# MB_power_supply.net
KiCad netlist of a schematic drawn in Altium Designer
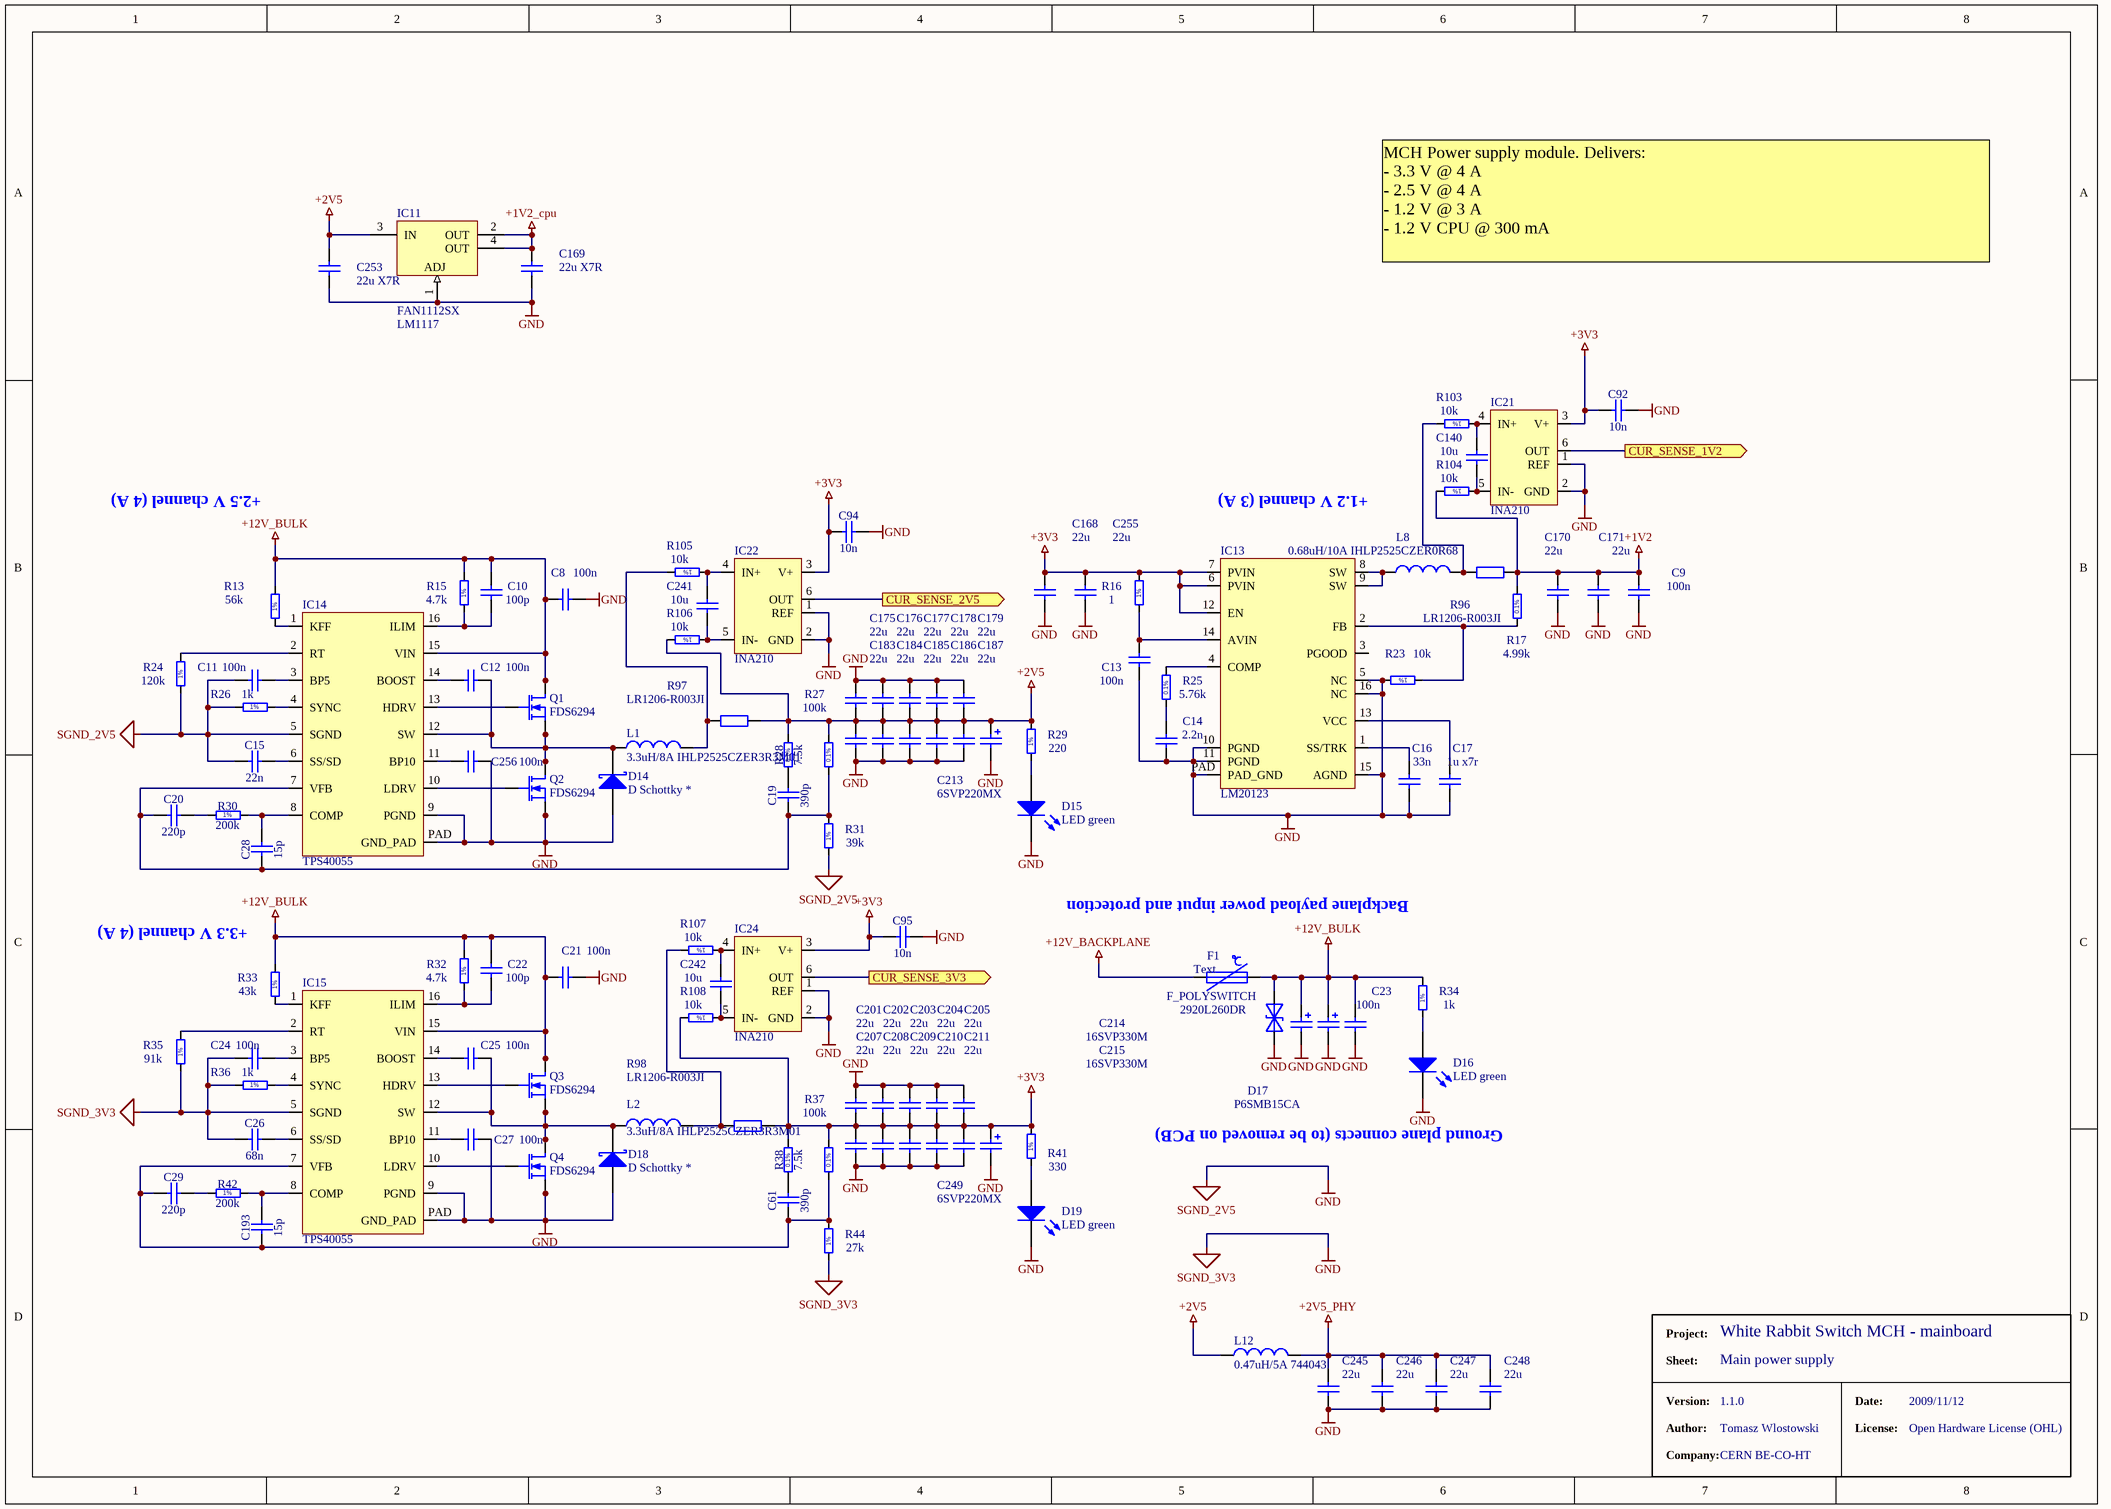
[diagram p0: MB_power_supply.SchDoc]

(export (version "E")
  (design (tool "Eeschema 10.0.6"))
  (components
    (comp (ref "C8")
      (value "100n")
      (footprint "CAPC1608X87N")
      (description "Non-polarised capacitor")
      (fields (field (name "PART NUMBER") "CC0603_100NF_50V_10%_X7R") (field (name "VOLTAGE") "50V"))
      (libsource (lib "Capacitors") (part "Capacitor - non polarized"))
    )
    (comp (ref "C9")
      (value "100n")
      (footprint "CAPC1608X87N")
      (description "Non-polarised capacitor")
      (fields (field (name "PART NUMBER") "CC0603_100NF_50V_10%_X7R") (field (name "VOLTAGE") "50V"))
      (libsource (lib "Capacitors") (part "Capacitor - non polarized"))
    )
    (comp (ref "C10")
      (value "100p")
      (footprint "CAPC1608X87N")
      (description "Non-polarised capacitor")
      (fields (field (name "PART NUMBER") "CC0603_100PF_50V_5%_NP0") (field (name "VOLTAGE") "50V"))
      (libsource (lib "Capacitors") (part "Capacitor - non polarized"))
    )
    (comp (ref "C11")
      (value "100n")
      (footprint "CAPC1608X87N")
      (description "Non-polarised capacitor")
      (fields (field (name "PART NUMBER") "CC0603_100NF_50V_10%_X7R") (field (name "VOLTAGE") "50V"))
      (libsource (lib "Capacitors") (part "Capacitor - non polarized"))
    )
    (comp (ref "C12")
      (value "100n")
      (footprint "CAPC1608X87N")
      (description "Non-polarised capacitor")
      (fields (field (name "PART NUMBER") "CC0603_100NF_50V_10%_X7R") (field (name "VOLTAGE") "50V"))
      (libsource (lib "Capacitors") (part "Capacitor - non polarized"))
    )
    (comp (ref "C13")
      (value "100n")
      (footprint "CAPC1608X87N")
      (description "Non-polarised capacitor")
      (fields (field (name "PART NUMBER") "CC0603_100NF_50V_10%_X7R") (field (name "VOLTAGE") "50V"))
      (libsource (lib "Capacitors") (part "Capacitor - non polarized"))
    )
    (comp (ref "C14")
      (value "2.2n")
      (footprint "CAPC1608X87N")
      (description "Non-polarised capacitor")
      (fields (field (name "PART NUMBER") "CC0603_2.2NF_50V_10%_X7R") (field (name "VOLTAGE") "50V"))
      (libsource (lib "Capacitors") (part "Capacitor - non polarized"))
    )
    (comp (ref "C15")
      (value "22n")
      (footprint "CAPC1608X87N")
      (description "Non-polarised capacitor")
      (fields (field (name "PART NUMBER") "CC0603_22NF_50V_10%_X7R") (field (name "VOLTAGE") "50V"))
      (libsource (lib "Capacitors") (part "Capacitor - non polarized"))
    )
    (comp (ref "C16")
      (value "33n")
      (footprint "CAPC1608X87N")
      (description "Non-polarised capacitor")
      (fields (field (name "PART NUMBER") "CC0603_33NF_25V_10%_X7R") (field (name "VOLTAGE") "25V"))
      (libsource (lib "Capacitors") (part "Capacitor - non polarized"))
    )
    (comp (ref "C17")
      (value "1u x7r")
      (footprint "CAPC1608X87N")
      (description "Non-polarised capacitor")
      (fields (field (name "PART NUMBER") "CC0603_1.0uF_16V_10%_X7R") (field (name "VOLTAGE") "16V"))
      (libsource (lib "Capacitors") (part "Capacitor - non polarized"))
    )
    (comp (ref "C19")
      (value "390p")
      (footprint "CAPC1608X87N")
      (description "Non-polarised capacitor")
      (fields (field (name "PART NUMBER") "CC0603_390PF_50V_5%_NP0") (field (name "VOLTAGE") "50V"))
      (libsource (lib "Capacitors") (part "Capacitor - non polarized"))
    )
    (comp (ref "C20")
      (value "220p")
      (footprint "CAPC1608X87N")
      (description "Non-polarised capacitor")
      (fields (field (name "PART NUMBER") "CC0603_220PF_50V_5%_NP0") (field (name "VOLTAGE") "50V"))
      (libsource (lib "Capacitors") (part "Capacitor - non polarized"))
    )
    (comp (ref "C21")
      (value "100n")
      (footprint "CAPC1608X87N")
      (description "Non-polarised capacitor")
      (fields (field (name "PART NUMBER") "CC0603_100NF_50V_10%_X7R") (field (name "VOLTAGE") "50V"))
      (libsource (lib "Capacitors") (part "Capacitor - non polarized"))
    )
    (comp (ref "C22")
      (value "100p")
      (footprint "CAPC1608X87N")
      (description "Non-polarised capacitor")
      (fields (field (name "PART NUMBER") "CC0603_100PF_50V_5%_NP0") (field (name "VOLTAGE") "50V"))
      (libsource (lib "Capacitors") (part "Capacitor - non polarized"))
    )
    (comp (ref "C23")
      (value "100n")
      (footprint "CAPC1608X87N")
      (description "Non-polarised capacitor")
      (fields (field (name "PART NUMBER") "CC0603_100NF_50V_10%_X7R") (field (name "VOLTAGE") "50V"))
      (libsource (lib "Capacitors") (part "Capacitor - non polarized"))
    )
    (comp (ref "C24")
      (value "100n")
      (footprint "CAPC1608X87N")
      (description "Non-polarised capacitor")
      (fields (field (name "PART NUMBER") "CC0603_100NF_50V_10%_X7R") (field (name "VOLTAGE") "50V"))
      (libsource (lib "Capacitors") (part "Capacitor - non polarized"))
    )
    (comp (ref "C25")
      (value "100n")
      (footprint "CAPC1608X87N")
      (description "Non-polarised capacitor")
      (fields (field (name "PART NUMBER") "CC0603_100NF_50V_10%_X7R") (field (name "VOLTAGE") "50V"))
      (libsource (lib "Capacitors") (part "Capacitor - non polarized"))
    )
    (comp (ref "C26")
      (value "68n")
      (footprint "CAPC1608X87N")
      (description "Non-polarised capacitor")
      (fields (field (name "PART NUMBER") "CC0603_68NF_16V_10%_X7R") (field (name "VOLTAGE") "16V"))
      (libsource (lib "Capacitors") (part "Capacitor - non polarized"))
    )
    (comp (ref "C27")
      (value "100n")
      (footprint "CAPC1608X87N")
      (description "Non-polarised capacitor")
      (fields (field (name "PART NUMBER") "CC0603_100NF_50V_10%_X7R") (field (name "VOLTAGE") "50V"))
      (libsource (lib "Capacitors") (part "Capacitor - non polarized"))
    )
    (comp (ref "C28")
      (value "15p")
      (footprint "CAPC1608X87N")
      (description "Non-polarised capacitor")
      (fields (field (name "PART NUMBER") "CC0603_15PF_50V_5%_NP0") (field (name "VOLTAGE") "50V"))
      (libsource (lib "Capacitors") (part "Capacitor - non polarized"))
    )
    (comp (ref "C29")
      (value "220p")
      (footprint "CAPC1608X87N")
      (description "Non-polarised capacitor")
      (fields (field (name "PART NUMBER") "CC0603_220PF_50V_5%_NP0") (field (name "VOLTAGE") "50V"))
      (libsource (lib "Capacitors") (part "Capacitor - non polarized"))
    )
    (comp (ref "C61")
      (value "390p")
      (footprint "CAPC1608X87N")
      (description "Non-polarised capacitor")
      (fields (field (name "PART NUMBER") "CC0603_390PF_50V_5%_NP0") (field (name "VOLTAGE") "50V"))
      (libsource (lib "Capacitors") (part "Capacitor - non polarized"))
    )
    (comp (ref "C92")
      (value "10n")
      (footprint "CAPC1608X87N")
      (description "Non-polarised capacitor")
      (fields (field (name "PART NUMBER") "CC0603_10NF_50V_10%_X7R") (field (name "VOLTAGE") "50V"))
      (libsource (lib "Capacitors") (part "Capacitor - non polarized"))
    )
    (comp (ref "C94")
      (value "10n")
      (footprint "CAPC1608X87N")
      (description "Non-polarised capacitor")
      (fields (field (name "PART NUMBER") "CC0603_10NF_50V_10%_X7R") (field (name "VOLTAGE") "50V"))
      (libsource (lib "Capacitors") (part "Capacitor - non polarized"))
    )
    (comp (ref "C95")
      (value "10n")
      (footprint "CAPC1608X87N")
      (description "Non-polarised capacitor")
      (fields (field (name "PART NUMBER") "CC0603_10NF_50V_10%_X7R") (field (name "VOLTAGE") "50V"))
      (libsource (lib "Capacitors") (part "Capacitor - non polarized"))
    )
    (comp (ref "C140")
      (value "10u")
      (footprint "CAPC1608X87N")
      (description "Non-polarised capacitor")
      (fields (field (name "PART NUMBER") "CC0603_10uF_6.3V_20%_X5R") (field (name "VOLTAGE") "6.3V"))
      (libsource (lib "Capacitors") (part "Capacitor - non polarized"))
    )
    (comp (ref "C168")
      (value "22u")
      (footprint "CC3216-1206")
      (description "Capacitor")
      (fields (field (name "Comment") "22u X7R"))
      (libsource (lib "wr_switch") (part "Cap"))
    )
    (comp (ref "C169")
      (value "22u X7R")
      (footprint "CC3216-1206")
      (description "Capacitor")
      (libsource (lib "wr_switch") (part "Cap"))
    )
    (comp (ref "C170")
      (value "22u")
      (footprint "CC3216-1206")
      (description "Capacitor")
      (fields (field (name "Comment") "22u X7R"))
      (libsource (lib "wr_switch") (part "Cap"))
    )
    (comp (ref "C171")
      (value "22u")
      (footprint "CC3216-1206")
      (description "Capacitor")
      (fields (field (name "Comment") "22u X7R"))
      (libsource (lib "wr_switch") (part "Cap"))
    )
    (comp (ref "C175")
      (value "22u")
      (footprint "CC3216-1206")
      (description "Capacitor")
      (fields (field (name "Comment") "22u X7R"))
      (libsource (lib "wr_switch") (part "Cap"))
    )
    (comp (ref "C176")
      (value "22u")
      (footprint "CC3216-1206")
      (description "Capacitor")
      (fields (field (name "Comment") "22u X7R"))
      (libsource (lib "wr_switch") (part "Cap"))
    )
    (comp (ref "C177")
      (value "22u")
      (footprint "CC3216-1206")
      (description "Capacitor")
      (fields (field (name "Comment") "22u X7R"))
      (libsource (lib "wr_switch") (part "Cap"))
    )
    (comp (ref "C178")
      (value "22u")
      (footprint "CC3216-1206")
      (description "Capacitor")
      (fields (field (name "Comment") "22u X7R"))
      (libsource (lib "wr_switch") (part "Cap"))
    )
    (comp (ref "C179")
      (value "22u")
      (footprint "CC3216-1206")
      (description "Capacitor")
      (fields (field (name "Comment") "22u X7R"))
      (libsource (lib "wr_switch") (part "Cap"))
    )
    (comp (ref "C183")
      (value "22u")
      (footprint "CC3216-1206")
      (description "Capacitor")
      (fields (field (name "Comment") "22u X7R"))
      (libsource (lib "wr_switch") (part "Cap"))
    )
    (comp (ref "C184")
      (value "22u")
      (footprint "CC3216-1206")
      (description "Capacitor")
      (fields (field (name "Comment") "22u X7R"))
      (libsource (lib "wr_switch") (part "Cap"))
    )
    (comp (ref "C185")
      (value "22u")
      (footprint "CC3216-1206")
      (description "Capacitor")
      (fields (field (name "Comment") "22u X7R"))
      (libsource (lib "wr_switch") (part "Cap"))
    )
    (comp (ref "C186")
      (value "22u")
      (footprint "CC3216-1206")
      (description "Capacitor")
      (fields (field (name "Comment") "22u X7R"))
      (libsource (lib "wr_switch") (part "Cap"))
    )
    (comp (ref "C187")
      (value "22u")
      (footprint "CC3216-1206")
      (description "Capacitor")
      (fields (field (name "Comment") "22u X7R"))
      (libsource (lib "wr_switch") (part "Cap"))
    )
    (comp (ref "C193")
      (value "15p")
      (footprint "CAPC1608X87N")
      (description "Non-polarised capacitor")
      (fields (field (name "PART NUMBER") "CC0603_15PF_50V_5%_NP0") (field (name "VOLTAGE") "50V"))
      (libsource (lib "Capacitors") (part "Capacitor - non polarized"))
    )
    (comp (ref "C201")
      (value "22u")
      (footprint "CC3216-1206")
      (description "Capacitor")
      (fields (field (name "Comment") "22u X7R"))
      (libsource (lib "wr_switch") (part "Cap"))
    )
    (comp (ref "C202")
      (value "22u")
      (footprint "CC3216-1206")
      (description "Capacitor")
      (fields (field (name "Comment") "22u X7R"))
      (libsource (lib "wr_switch") (part "Cap"))
    )
    (comp (ref "C203")
      (value "22u")
      (footprint "CC3216-1206")
      (description "Capacitor")
      (fields (field (name "Comment") "22u X7R"))
      (libsource (lib "wr_switch") (part "Cap"))
    )
    (comp (ref "C204")
      (value "22u")
      (footprint "CC3216-1206")
      (description "Capacitor")
      (fields (field (name "Comment") "22u X7R"))
      (libsource (lib "wr_switch") (part "Cap"))
    )
    (comp (ref "C205")
      (value "22u")
      (footprint "CC3216-1206")
      (description "Capacitor")
      (fields (field (name "Comment") "22u X7R"))
      (libsource (lib "wr_switch") (part "Cap"))
    )
    (comp (ref "C207")
      (value "22u")
      (footprint "CC3216-1206")
      (description "Capacitor")
      (fields (field (name "Comment") "22u X7R"))
      (libsource (lib "wr_switch") (part "Cap"))
    )
    (comp (ref "C208")
      (value "22u")
      (footprint "CC3216-1206")
      (description "Capacitor")
      (fields (field (name "Comment") "22u X7R"))
      (libsource (lib "wr_switch") (part "Cap"))
    )
    (comp (ref "C209")
      (value "22u")
      (footprint "CC3216-1206")
      (description "Capacitor")
      (fields (field (name "Comment") "22u X7R"))
      (libsource (lib "wr_switch") (part "Cap"))
    )
    (comp (ref "C210")
      (value "22u")
      (footprint "CC3216-1206")
      (description "Capacitor")
      (fields (field (name "Comment") "22u X7R"))
      (libsource (lib "wr_switch") (part "Cap"))
    )
    (comp (ref "C211")
      (value "22u")
      (footprint "CC3216-1206")
      (description "Capacitor")
      (fields (field (name "Comment") "22u X7R"))
      (libsource (lib "wr_switch") (part "Cap"))
    )
    (comp (ref "C213")
      (value "6SVP220MX")
      (footprint "OSCON_E7")
      (description "Polarized Capacitor (Radial)")
      (fields (field (name "Comment") "220u/6.3V 6SVP220MX"))
      (libsource (lib "wr_switch") (part "Cap Pol1"))
    )
    (comp (ref "C214")
      (value "16SVP330M")
      (footprint "OSCON_F12")
      (description "Polarized Capacitor (Radial)")
      (fields (field (name "Comment") "330u/16V 16SVP330M"))
      (libsource (lib "wr_switch") (part "Cap Pol1"))
    )
    (comp (ref "C215")
      (value "16SVP330M")
      (footprint "OSCON_F12")
      (description "Polarized Capacitor (Radial)")
      (fields (field (name "Comment") "330u/16V 16SVP330M"))
      (libsource (lib "wr_switch") (part "Cap Pol1"))
    )
    (comp (ref "C241")
      (value "10u")
      (footprint "CAPC1608X87N")
      (description "Non-polarised capacitor")
      (fields (field (name "PART NUMBER") "CC0603_10uF_6.3V_20%_X5R") (field (name "VOLTAGE") "6.3V"))
      (libsource (lib "Capacitors") (part "Capacitor - non polarized"))
    )
    (comp (ref "C242")
      (value "10u")
      (footprint "CAPC1608X87N")
      (description "Non-polarised capacitor")
      (fields (field (name "PART NUMBER") "CC0603_10uF_6.3V_20%_X5R") (field (name "VOLTAGE") "6.3V"))
      (libsource (lib "Capacitors") (part "Capacitor - non polarized"))
    )
    (comp (ref "C245")
      (value "22u")
      (footprint "CC3216-1206")
      (description "Capacitor")
      (fields (field (name "Comment") "22u X7R"))
      (libsource (lib "wr_switch") (part "Cap"))
    )
    (comp (ref "C246")
      (value "22u")
      (footprint "CC3216-1206")
      (description "Capacitor")
      (fields (field (name "Comment") "22u X7R"))
      (libsource (lib "wr_switch") (part "Cap"))
    )
    (comp (ref "C247")
      (value "22u")
      (footprint "CC3216-1206")
      (description "Capacitor")
      (fields (field (name "Comment") "22u X7R"))
      (libsource (lib "wr_switch") (part "Cap"))
    )
    (comp (ref "C248")
      (value "22u")
      (footprint "CC3216-1206")
      (description "Capacitor")
      (fields (field (name "Comment") "22u X7R"))
      (libsource (lib "wr_switch") (part "Cap"))
    )
    (comp (ref "C249")
      (value "6SVP220MX")
      (footprint "OSCON_E7")
      (description "Polarized Capacitor (Radial)")
      (fields (field (name "Comment") "220u/6.3V 6SVP220MX"))
      (libsource (lib "wr_switch") (part "Cap Pol1"))
    )
    (comp (ref "C253")
      (value "22u X7R")
      (footprint "CC3216-1206")
      (description "Capacitor")
      (libsource (lib "wr_switch") (part "Cap"))
    )
    (comp (ref "C255")
      (value "22u")
      (footprint "CC3216-1206")
      (description "Capacitor")
      (fields (field (name "Comment") "22u X7R"))
      (libsource (lib "wr_switch") (part "Cap"))
    )
    (comp (ref "C256")
      (value "100n")
      (footprint "CAPC1608X87N")
      (description "Non-polarised capacitor")
      (fields (field (name "PART NUMBER") "CC0603_100NF_50V_10%_X7R") (field (name "VOLTAGE") "50V"))
      (libsource (lib "Capacitors") (part "Capacitor - non polarized"))
    )
    (comp (ref "D14")
      (value "D Schottky *")
      (footprint "CD3216-1206")
      (description "Schottky Diode")
      (libsource (lib "wr_switch") (part "D Schottky"))
    )
    (comp (ref "D15")
      (value "LED green")
      (footprint "CD1608-0603")
      (description "Red chip LED")
      (libsource (lib "wr_switch") (part "LED0"))
    )
    (comp (ref "D16")
      (value "LED green")
      (footprint "CD1608-0603")
      (description "Red chip LED")
      (libsource (lib "wr_switch") (part "LED0"))
    )
    (comp (ref "D17")
      (value "P6SMB15CA")
      (footprint "footprints:DO-214AA/SMB")
      (description "transil 600W")
      (libsource (lib "wr_switch") (part "D_TRANSIL_SMD_0.6KW"))
    )
    (comp (ref "D18")
      (value "D Schottky *")
      (footprint "CD3216-1206")
      (description "Schottky Diode")
      (libsource (lib "wr_switch") (part "D Schottky"))
    )
    (comp (ref "D19")
      (value "LED green")
      (footprint "CD1608-0603")
      (description "Red chip LED")
      (libsource (lib "wr_switch") (part "LED0"))
    )
    (comp (ref "F1")
      (value "F_POLYSWITCH")
      (footprint "PTC_SMD_1812")
      (description "polymer FUSE")
      (fields (field (name "ALTIUM_VALUE") "2920L260DR"))
      (libsource (lib "wr_switch") (part "F_POLYSWITCH"))
    )
    (comp (ref "IC11")
      (value "FAN1112SX")
      (footprint "SOT223-4L")
      (description "Three-Terminal Adjustable Output Positive Voltage Regulator")
      (fields (field (name "ALTIUM_VALUE") "LM1117"))
      (libsource (lib "wr_switch") (part "1117"))
    )
    (comp (ref "IC13")
      (value "LM20123")
      (footprint "eTSSOP_16_MX")
      (description "National Semiconductor 3A integrated synchronous buck converter")
      (libsource (lib "wr_switch") (part "LM20123"))
    )
    (comp (ref "IC14")
      (value "TPS40055")
      (footprint "TI_PWP_16")
      (description "TI synchronous buck controller")
      (libsource (lib "wr_switch") (part "TPS4005X"))
    )
    (comp (ref "IC15")
      (value "TPS40055")
      (footprint "TI_PWP_16")
      (description "TI synchronous buck controller")
      (libsource (lib "wr_switch") (part "TPS4005X"))
    )
    (comp (ref "IC21")
      (value "INA210")
      (footprint "TI_6sc70")
      (description "High/low side current monitor")
      (libsource (lib "wr_switch") (part "INA210_214"))
    )
    (comp (ref "IC22")
      (value "INA210")
      (footprint "TI_6sc70")
      (description "High/low side current monitor")
      (libsource (lib "wr_switch") (part "INA210_214"))
    )
    (comp (ref "IC24")
      (value "INA210")
      (footprint "TI_6sc70")
      (description "High/low side current monitor")
      (libsource (lib "wr_switch") (part "INA210_214"))
    )
    (comp (ref "L1")
      (value "3.3uH/8A IHLP2525CZER3R3M01")
      (footprint "IHLP2525")
      (description "Vishay 16A 2.2u inductor")
      (libsource (lib "wr_switch") (part "L_IHLP2525_0.68u"))
    )
    (comp (ref "L2")
      (value "3.3uH/8A IHLP2525CZER3R3M01")
      (footprint "IHLP2525")
      (description "Vishay 16A 2.2u inductor")
      (libsource (lib "wr_switch") (part "L_IHLP2525_0.68u"))
    )
    (comp (ref "L8")
      (value "0.68uH/10A IHLP2525CZER0R68")
      (footprint "IHLP2525")
      (description "Vishay 16A 2.2u inductor")
      (libsource (lib "wr_switch") (part "L_IHLP2525_0.68u"))
    )
    (comp (ref "L12")
      (value "0.47uH/5A 744043")
      (footprint "IND_WURTH_744042_MH")
      (description "Wuerth small footprint SMD power inductor")
      (libsource (lib "wr_switch") (part "L_WUERTH_744043"))
    )
    (comp (ref "Q1")
      (value "FDS6294")
      (footprint "SOIC127P600-8AL")
      (description "18A 8mOhm N-Channel MOSFET")
      (libsource (lib "wr_switch") (part "Q_SI7860"))
    )
    (comp (ref "Q2")
      (value "FDS6294")
      (footprint "SOIC127P600-8AL")
      (description "18A 8mOhm N-Channel MOSFET")
      (libsource (lib "wr_switch") (part "Q_SI7860"))
    )
    (comp (ref "Q3")
      (value "FDS6294")
      (footprint "SOIC127P600-8AL")
      (description "18A 8mOhm N-Channel MOSFET")
      (libsource (lib "wr_switch") (part "Q_SI7860"))
    )
    (comp (ref "Q4")
      (value "FDS6294")
      (footprint "SOIC127P600-8AL")
      (description "18A 8mOhm N-Channel MOSFET")
      (libsource (lib "wr_switch") (part "Q_SI7860"))
    )
    (comp (ref "R13")
      (value "56k")
      (footprint "RESC1608X55N")
      (description "Resistor - 1%")
      (fields (field (name "PART NUMBER") "R0603_56K_1%_0.1W_100PPM") (field (name "POWER") "0.1W"))
      (libsource (lib "Resistors") (part "Resistor - 1%"))
    )
    (comp (ref "R15")
      (value "4.7k")
      (footprint "RESC1608X55N")
      (description "Resistor - 1%")
      (fields (field (name "PART NUMBER") "R0603_4K7_1%_0.1W_100PPM") (field (name "POWER") "0.1W"))
      (libsource (lib "Resistors") (part "Resistor - 1%"))
    )
    (comp (ref "R16")
      (value "1")
      (footprint "RESC1608X55N")
      (description "Resistor - 1%")
      (fields (field (name "PART NUMBER") "R0603_1R_1%_0.1W_100PPM") (field (name "POWER") "0.1W"))
      (libsource (lib "Resistors") (part "Resistor - 1%"))
    )
    (comp (ref "R17")
      (value "4.99k")
      (footprint "RESC1608X55N")
      (description "Resistor - 0.1%")
      (fields (field (name "PART NUMBER") "R0603_4K99_0.1%_0.063W_10PPM") (field (name "POWER") "0.063W"))
      (libsource (lib "Resistors") (part "Resistor - 0.1%"))
    )
    (comp (ref "R23")
      (value "10k")
      (footprint "RESC1608X55N")
      (description "Resistor - 1%")
      (fields (field (name "PART NUMBER") "R0603_10K_1%_0.1W_100PPM") (field (name "POWER") "0.1W"))
      (libsource (lib "Resistors") (part "Resistor - 1%"))
    )
    (comp (ref "R24")
      (value "120k")
      (footprint "RESC1608X55N")
      (description "Resistor - 1%")
      (fields (field (name "PART NUMBER") "R0603_120K_1%_0.1W_100PPM") (field (name "POWER") "0.1W"))
      (libsource (lib "Resistors") (part "Resistor - 1%"))
    )
    (comp (ref "R25")
      (value "5.76k")
      (footprint "RESC1608X55N")
      (description "Resistor - 0.1%")
      (fields (field (name "PART NUMBER") "R0603_5K76_0.1%_0.063W_10PPM") (field (name "POWER") "0.063W"))
      (libsource (lib "Resistors") (part "Resistor - 0.1%"))
    )
    (comp (ref "R26")
      (value "1k")
      (footprint "RESC1608X55N")
      (description "Resistor - 1%")
      (fields (field (name "PART NUMBER") "R0603_1K_1%_0.1W_100PPM") (field (name "POWER") "0.1W"))
      (libsource (lib "Resistors") (part "Resistor - 1%"))
    )
    (comp (ref "R27")
      (value "100k")
      (footprint "RESC1608X55N")
      (description "Resistor - 0.1%")
      (fields (field (name "PART NUMBER") "R0603_100K_0.1%_0.063W_10PPM") (field (name "POWER") "0.063W"))
      (libsource (lib "Resistors") (part "Resistor - 0.1%"))
    )
    (comp (ref "R28")
      (value "7.5k")
      (footprint "RESC1608X55N")
      (description "Resistor - 0.1%")
      (fields (field (name "PART NUMBER") "R0603_7K5_0.1%_0.063W_10PPM") (field (name "POWER") "0.063W"))
      (libsource (lib "Resistors") (part "Resistor - 0.1%"))
    )
    (comp (ref "R29")
      (value "220")
      (footprint "RESC1608X55N")
      (description "Resistor - 1%")
      (fields (field (name "PART NUMBER") "R0603_220R_1%_0.1W_100PPM") (field (name "POWER") "0.1W"))
      (libsource (lib "Resistors") (part "Resistor - 1%"))
    )
    (comp (ref "R30")
      (value "200k")
      (footprint "RESC1608X55N")
      (description "Resistor - 1%")
      (fields (field (name "PART NUMBER") "R0603_200K_1%_0.1W_100PPM") (field (name "POWER") "0.1W"))
      (libsource (lib "Resistors") (part "Resistor - 1%"))
    )
    (comp (ref "R31")
      (value "39k")
      (footprint "RESC1608X55N")
      (description "Resistor - 1%")
      (fields (field (name "PART NUMBER") "R0603_39K_1%_0.1W_100PPM") (field (name "POWER") "0.1W"))
      (libsource (lib "Resistors") (part "Resistor - 1%"))
    )
    (comp (ref "R32")
      (value "4.7k")
      (footprint "RESC1608X55N")
      (description "Resistor - 1%")
      (fields (field (name "PART NUMBER") "R0603_4K7_1%_0.1W_100PPM") (field (name "POWER") "0.1W"))
      (libsource (lib "Resistors") (part "Resistor - 1%"))
    )
    (comp (ref "R33")
      (value "43k")
      (footprint "RESC1608X55N")
      (description "Resistor - 1%")
      (fields (field (name "PART NUMBER") "R0603_43K_1%_0.1W_100PPM") (field (name "POWER") "0.1W"))
      (libsource (lib "Resistors") (part "Resistor - 1%"))
    )
    (comp (ref "R34")
      (value "1k")
      (footprint "RESC1005X40N")
      (description "Resistor - 1%")
      (fields (field (name "PART NUMBER") "R0402_1K_1%_0.0625W_100PPM") (field (name "POWER") "0.0625W"))
      (libsource (lib "Resistors") (part "Resistor - 1%"))
    )
    (comp (ref "R35")
      (value "91k")
      (footprint "RESC1608X55N")
      (description "Resistor - 1%")
      (fields (field (name "PART NUMBER") "R0603_91K_1%_0.1W_100PPM") (field (name "POWER") "0.1W"))
      (libsource (lib "Resistors") (part "Resistor - 1%"))
    )
    (comp (ref "R36")
      (value "1k")
      (footprint "RESC1608X55N")
      (description "Resistor - 1%")
      (fields (field (name "PART NUMBER") "R0603_1K_1%_0.1W_100PPM") (field (name "POWER") "0.1W"))
      (libsource (lib "Resistors") (part "Resistor - 1%"))
    )
    (comp (ref "R37")
      (value "100k")
      (footprint "RESC1608X55N")
      (description "Resistor - 0.1%")
      (fields (field (name "PART NUMBER") "R0603_100K_0.1%_0.063W_10PPM") (field (name "POWER") "0.063W"))
      (libsource (lib "Resistors") (part "Resistor - 0.1%"))
    )
    (comp (ref "R38")
      (value "7.5k")
      (footprint "RESC1608X55N")
      (description "Resistor - 0.1%")
      (fields (field (name "PART NUMBER") "R0603_7K5_0.1%_0.063W_10PPM") (field (name "POWER") "0.063W"))
      (libsource (lib "Resistors") (part "Resistor - 0.1%"))
    )
    (comp (ref "R41")
      (value "330")
      (footprint "RESC1608X55N")
      (description "Resistor - 1%")
      (fields (field (name "PART NUMBER") "R0603_330R_1%_0.1W_100PPM") (field (name "POWER") "0.1W"))
      (libsource (lib "Resistors") (part "Resistor - 1%"))
    )
    (comp (ref "R42")
      (value "200k")
      (footprint "RESC1608X55N")
      (description "Resistor - 1%")
      (fields (field (name "PART NUMBER") "R0603_200K_1%_0.1W_100PPM") (field (name "POWER") "0.1W"))
      (libsource (lib "Resistors") (part "Resistor - 1%"))
    )
    (comp (ref "R44")
      (value "27k")
      (footprint "RESC1608X55N")
      (description "Resistor - 1%")
      (fields (field (name "PART NUMBER") "R0603_27K_1%_0.1W_100PPM") (field (name "POWER") "0.1W"))
      (libsource (lib "Resistors") (part "Resistor - 1%"))
    )
    (comp (ref "R96")
      (value "LR1206-R003JI")
      (footprint "CR3216-1206")
      (description "Resistor")
      (fields (field (name "Comment") "0.003R LR1206-R003JI"))
      (libsource (lib "Miscellaneous Devices") (part "Res2"))
    )
    (comp (ref "R97")
      (value "LR1206-R003JI")
      (footprint "CR3216-1206")
      (description "Resistor")
      (fields (field (name "Comment") "0.003R LR1206-R003JI"))
      (libsource (lib "Miscellaneous Devices") (part "Res2"))
    )
    (comp (ref "R98")
      (value "LR1206-R003JI")
      (footprint "CR3216-1206")
      (description "Resistor")
      (fields (field (name "Comment") "0.003R LR1206-R003JI"))
      (libsource (lib "Miscellaneous Devices") (part "Res2"))
    )
    (comp (ref "R103")
      (value "10k")
      (footprint "RESC1005X40N")
      (description "Resistor - 1%")
      (fields (field (name "PART NUMBER") "R0402_10K_1%_0.0625W_100PPM") (field (name "POWER") "0.0625W"))
      (libsource (lib "Resistors") (part "Resistor - 1%"))
    )
    (comp (ref "R104")
      (value "10k")
      (footprint "RESC1005X40N")
      (description "Resistor - 1%")
      (fields (field (name "PART NUMBER") "R0402_10K_1%_0.0625W_100PPM") (field (name "POWER") "0.0625W"))
      (libsource (lib "Resistors") (part "Resistor - 1%"))
    )
    (comp (ref "R105")
      (value "10k")
      (footprint "RESC1005X40N")
      (description "Resistor - 1%")
      (fields (field (name "PART NUMBER") "R0402_10K_1%_0.0625W_100PPM") (field (name "POWER") "0.0625W"))
      (libsource (lib "Resistors") (part "Resistor - 1%"))
    )
    (comp (ref "R106")
      (value "10k")
      (footprint "RESC1005X40N")
      (description "Resistor - 1%")
      (fields (field (name "PART NUMBER") "R0402_10K_1%_0.0625W_100PPM") (field (name "POWER") "0.0625W"))
      (libsource (lib "Resistors") (part "Resistor - 1%"))
    )
    (comp (ref "R107")
      (value "10k")
      (footprint "RESC1005X40N")
      (description "Resistor - 1%")
      (fields (field (name "PART NUMBER") "R0402_10K_1%_0.0625W_100PPM") (field (name "POWER") "0.0625W"))
      (libsource (lib "Resistors") (part "Resistor - 1%"))
    )
    (comp (ref "R108")
      (value "10k")
      (footprint "RESC1005X40N")
      (description "Resistor - 1%")
      (fields (field (name "PART NUMBER") "R0402_10K_1%_0.0625W_100PPM") (field (name "POWER") "0.0625W"))
      (libsource (lib "Resistors") (part "Resistor - 1%"))
    )
  )
  (nets
    (net (code "1") (name "+1V2") (class "Default")
      (node (ref "C170") (pin "2") (pinfunction "2_2") (pintype "passive"))
      (node (ref "C171") (pin "2") (pinfunction "2_2") (pintype "passive"))
      (node (ref "C9") (pin "2") (pinfunction "2_2") (pintype "passive"))
      (node (ref "R104") (pin "2") (pinfunction "2_2") (pintype "passive"))
      (node (ref "R17") (pin "2") (pinfunction "2_2") (pintype "passive"))
      (node (ref "R96") (pin "1") (pinfunction "1_1") (pintype "passive"))
    )
    (net (code "2") (name "+1V2_cpu") (class "Default")
      (node (ref "C169") (pin "2") (pinfunction "2_2") (pintype "passive"))
      (node (ref "IC11") (pin "2") (pinfunction "OUT_2") (pintype "power_in"))
      (node (ref "IC11") (pin "4") (pinfunction "OUT_4") (pintype "power_in"))
    )
    (net (code "3") (name "+2V5") (class "Default")
      (node (ref "C175") (pin "1") (pinfunction "1_1") (pintype "passive"))
      (node (ref "C176") (pin "1") (pinfunction "1_1") (pintype "passive"))
      (node (ref "C177") (pin "1") (pinfunction "1_1") (pintype "passive"))
      (node (ref "C178") (pin "1") (pinfunction "1_1") (pintype "passive"))
      (node (ref "C179") (pin "1") (pinfunction "1_1") (pintype "passive"))
      (node (ref "C183") (pin "2") (pinfunction "2_2") (pintype "passive"))
      (node (ref "C184") (pin "2") (pinfunction "2_2") (pintype "passive"))
      (node (ref "C185") (pin "2") (pinfunction "2_2") (pintype "passive"))
      (node (ref "C186") (pin "2") (pinfunction "2_2") (pintype "passive"))
      (node (ref "C187") (pin "2") (pinfunction "2_2") (pintype "passive"))
      (node (ref "C213") (pin "1") (pinfunction "1_1") (pintype "passive"))
      (node (ref "C253") (pin "2") (pinfunction "2_2") (pintype "passive"))
      (node (ref "IC11") (pin "3") (pinfunction "IN_3") (pintype "power_in"))
      (node (ref "L12") (pin "1") (pinfunction "1_1") (pintype "passive"))
      (node (ref "R106") (pin "2") (pinfunction "2_2") (pintype "passive"))
      (node (ref "R27") (pin "2") (pinfunction "2_2") (pintype "passive"))
      (node (ref "R28") (pin "2") (pinfunction "2_2") (pintype "passive"))
      (node (ref "R29") (pin "2") (pinfunction "2_2") (pintype "passive"))
      (node (ref "R97") (pin "1") (pinfunction "1_1") (pintype "passive"))
    )
    (net (code "4") (name "+2V5_PHY") (class "Default")
      (node (ref "C245") (pin "2") (pinfunction "2_2") (pintype "passive"))
      (node (ref "C246") (pin "2") (pinfunction "2_2") (pintype "passive"))
      (node (ref "C247") (pin "2") (pinfunction "2_2") (pintype "passive"))
      (node (ref "C248") (pin "2") (pinfunction "2_2") (pintype "passive"))
      (node (ref "L12") (pin "2") (pinfunction "2_2") (pintype "passive"))
    )
    (net (code "5") (name "+3V3") (class "Default")
      (node (ref "C168") (pin "2") (pinfunction "2_2") (pintype "passive"))
      (node (ref "C201") (pin "2") (pinfunction "2_2") (pintype "passive"))
      (node (ref "C202") (pin "2") (pinfunction "2_2") (pintype "passive"))
      (node (ref "C203") (pin "2") (pinfunction "2_2") (pintype "passive"))
      (node (ref "C204") (pin "2") (pinfunction "2_2") (pintype "passive"))
      (node (ref "C205") (pin "2") (pinfunction "2_2") (pintype "passive"))
      (node (ref "C207") (pin "1") (pinfunction "1_1") (pintype "passive"))
      (node (ref "C208") (pin "1") (pinfunction "1_1") (pintype "passive"))
      (node (ref "C209") (pin "1") (pinfunction "1_1") (pintype "passive"))
      (node (ref "C210") (pin "1") (pinfunction "1_1") (pintype "passive"))
      (node (ref "C211") (pin "1") (pinfunction "1_1") (pintype "passive"))
      (node (ref "C249") (pin "1") (pinfunction "1_1") (pintype "passive"))
      (node (ref "C255") (pin "2") (pinfunction "2_2") (pintype "passive"))
      (node (ref "C92") (pin "1") (pinfunction "1_1") (pintype "passive"))
      (node (ref "C94") (pin "1") (pinfunction "1_1") (pintype "passive"))
      (node (ref "C95") (pin "1") (pinfunction "1_1") (pintype "passive"))
      (node (ref "IC13") (pin "12") (pinfunction "EN_12") (pintype "passive"))
      (node (ref "IC13") (pin "6") (pinfunction "PVIN_6") (pintype "passive"))
      (node (ref "IC13") (pin "7") (pinfunction "PVIN_7") (pintype "passive"))
      (node (ref "IC21") (pin "3") (pinfunction "V+_3") (pintype "power_in"))
      (node (ref "IC22") (pin "3") (pinfunction "V+_3") (pintype "power_in"))
      (node (ref "IC24") (pin "3") (pinfunction "V+_3") (pintype "power_in"))
      (node (ref "R108") (pin "2") (pinfunction "2_2") (pintype "passive"))
      (node (ref "R16") (pin "2") (pinfunction "2_2") (pintype "passive"))
      (node (ref "R37") (pin "2") (pinfunction "2_2") (pintype "passive"))
      (node (ref "R38") (pin "2") (pinfunction "2_2") (pintype "passive"))
      (node (ref "R41") (pin "2") (pinfunction "2_2") (pintype "passive"))
      (node (ref "R98") (pin "1") (pinfunction "1_1") (pintype "passive"))
    )
    (net (code "6") (name "+12V_BACKPLANE") (class "Default")
      (node (ref "F1") (pin "1") (pinfunction "1_1") (pintype "passive"))
    )
    (net (code "7") (name "+12V_BULK") (class "Default")
      (node (ref "C10") (pin "2") (pinfunction "2_2") (pintype "passive"))
      (node (ref "C21") (pin "1") (pinfunction "1_1") (pintype "passive"))
      (node (ref "C214") (pin "1") (pinfunction "1_1") (pintype "passive"))
      (node (ref "C215") (pin "1") (pinfunction "1_1") (pintype "passive"))
      (node (ref "C22") (pin "2") (pinfunction "2_2") (pintype "passive"))
      (node (ref "C23") (pin "2") (pinfunction "2_2") (pintype "passive"))
      (node (ref "C8") (pin "1") (pinfunction "1_1") (pintype "passive"))
      (node (ref "D17") (pin "K") (pinfunction "K_K") (pintype "passive"))
      (node (ref "F1") (pin "2") (pinfunction "2_2") (pintype "passive"))
      (node (ref "IC14") (pin "15") (pinfunction "VIN_15") (pintype "passive"))
      (node (ref "IC15") (pin "15") (pinfunction "VIN_15") (pintype "passive"))
      (node (ref "Q1") (pin "5") (pinfunction "D_5") (pintype "passive"))
      (node (ref "Q1") (pin "6") (pinfunction "D_6") (pintype "passive"))
      (node (ref "Q1") (pin "7") (pinfunction "D_7") (pintype "passive"))
      (node (ref "Q1") (pin "8") (pinfunction "D_8") (pintype "passive"))
      (node (ref "Q3") (pin "5") (pinfunction "D_5") (pintype "passive"))
      (node (ref "Q3") (pin "6") (pinfunction "D_6") (pintype "passive"))
      (node (ref "Q3") (pin "7") (pinfunction "D_7") (pintype "passive"))
      (node (ref "Q3") (pin "8") (pinfunction "D_8") (pintype "passive"))
      (node (ref "R13") (pin "2") (pinfunction "2_2") (pintype "passive"))
      (node (ref "R15") (pin "2") (pinfunction "2_2") (pintype "passive"))
      (node (ref "R32") (pin "2") (pinfunction "2_2") (pintype "passive"))
      (node (ref "R33") (pin "2") (pinfunction "2_2") (pintype "passive"))
      (node (ref "R34") (pin "2") (pinfunction "2_2") (pintype "passive"))
    )
    (net (code "8") (name "/CUR_SENSE_1V2") (class "Default")
      (node (ref "IC21") (pin "6") (pinfunction "OUT_6") (pintype "power_in"))
    )
    (net (code "9") (name "/CUR_SENSE_2V5") (class "Default")
      (node (ref "IC22") (pin "6") (pinfunction "OUT_6") (pintype "power_in"))
    )
    (net (code "10") (name "/CUR_SENSE_3V3") (class "Default")
      (node (ref "IC24") (pin "6") (pinfunction "OUT_6") (pintype "power_in"))
    )
    (net (code "11") (name "GND") (class "Default")
      (node (ref "C11") (pin "1") (pinfunction "1_1") (pintype "passive"))
      (node (ref "C13") (pin "1") (pinfunction "1_1") (pintype "passive"))
      (node (ref "C14") (pin "1") (pinfunction "1_1") (pintype "passive"))
      (node (ref "C15") (pin "1") (pinfunction "1_1") (pintype "passive"))
      (node (ref "C16") (pin "1") (pinfunction "1_1") (pintype "passive"))
      (node (ref "C168") (pin "1") (pinfunction "1_1") (pintype "passive"))
      (node (ref "C169") (pin "1") (pinfunction "1_1") (pintype "passive"))
      (node (ref "C17") (pin "1") (pinfunction "1_1") (pintype "passive"))
      (node (ref "C170") (pin "1") (pinfunction "1_1") (pintype "passive"))
      (node (ref "C171") (pin "1") (pinfunction "1_1") (pintype "passive"))
      (node (ref "C175") (pin "2") (pinfunction "2_2") (pintype "passive"))
      (node (ref "C176") (pin "2") (pinfunction "2_2") (pintype "passive"))
      (node (ref "C177") (pin "2") (pinfunction "2_2") (pintype "passive"))
      (node (ref "C178") (pin "2") (pinfunction "2_2") (pintype "passive"))
      (node (ref "C179") (pin "2") (pinfunction "2_2") (pintype "passive"))
      (node (ref "C183") (pin "1") (pinfunction "1_1") (pintype "passive"))
      (node (ref "C184") (pin "1") (pinfunction "1_1") (pintype "passive"))
      (node (ref "C185") (pin "1") (pinfunction "1_1") (pintype "passive"))
      (node (ref "C186") (pin "1") (pinfunction "1_1") (pintype "passive"))
      (node (ref "C187") (pin "1") (pinfunction "1_1") (pintype "passive"))
      (node (ref "C201") (pin "1") (pinfunction "1_1") (pintype "passive"))
      (node (ref "C202") (pin "1") (pinfunction "1_1") (pintype "passive"))
      (node (ref "C203") (pin "1") (pinfunction "1_1") (pintype "passive"))
      (node (ref "C204") (pin "1") (pinfunction "1_1") (pintype "passive"))
      (node (ref "C205") (pin "1") (pinfunction "1_1") (pintype "passive"))
      (node (ref "C207") (pin "2") (pinfunction "2_2") (pintype "passive"))
      (node (ref "C208") (pin "2") (pinfunction "2_2") (pintype "passive"))
      (node (ref "C209") (pin "2") (pinfunction "2_2") (pintype "passive"))
      (node (ref "C21") (pin "2") (pinfunction "2_2") (pintype "passive"))
      (node (ref "C210") (pin "2") (pinfunction "2_2") (pintype "passive"))
      (node (ref "C211") (pin "2") (pinfunction "2_2") (pintype "passive"))
      (node (ref "C213") (pin "2") (pinfunction "2_2") (pintype "passive"))
      (node (ref "C214") (pin "2") (pinfunction "2_2") (pintype "passive"))
      (node (ref "C215") (pin "2") (pinfunction "2_2") (pintype "passive"))
      (node (ref "C23") (pin "1") (pinfunction "1_1") (pintype "passive"))
      (node (ref "C24") (pin "1") (pinfunction "1_1") (pintype "passive"))
      (node (ref "C245") (pin "1") (pinfunction "1_1") (pintype "passive"))
      (node (ref "C246") (pin "1") (pinfunction "1_1") (pintype "passive"))
      (node (ref "C247") (pin "1") (pinfunction "1_1") (pintype "passive"))
      (node (ref "C248") (pin "1") (pinfunction "1_1") (pintype "passive"))
      (node (ref "C249") (pin "2") (pinfunction "2_2") (pintype "passive"))
      (node (ref "C253") (pin "1") (pinfunction "1_1") (pintype "passive"))
      (node (ref "C255") (pin "1") (pinfunction "1_1") (pintype "passive"))
      (node (ref "C256") (pin "2") (pinfunction "2_2") (pintype "passive"))
      (node (ref "C26") (pin "1") (pinfunction "1_1") (pintype "passive"))
      (node (ref "C27") (pin "2") (pinfunction "2_2") (pintype "passive"))
      (node (ref "C8") (pin "2") (pinfunction "2_2") (pintype "passive"))
      (node (ref "C9") (pin "1") (pinfunction "1_1") (pintype "passive"))
      (node (ref "C92") (pin "2") (pinfunction "2_2") (pintype "passive"))
      (node (ref "C94") (pin "2") (pinfunction "2_2") (pintype "passive"))
      (node (ref "C95") (pin "2") (pinfunction "2_2") (pintype "passive"))
      (node (ref "D14") (pin "1") (pinfunction "A_1") (pintype "passive"))
      (node (ref "D15") (pin "2") (pinfunction "K_2") (pintype "passive"))
      (node (ref "D16") (pin "2") (pinfunction "K_2") (pintype "passive"))
      (node (ref "D17") (pin "A") (pinfunction "A_A") (pintype "passive"))
      (node (ref "D18") (pin "1") (pinfunction "A_1") (pintype "passive"))
      (node (ref "D19") (pin "2") (pinfunction "K_2") (pintype "passive"))
      (node (ref "IC11") (pin "1") (pinfunction "ADJ_1") (pintype "input"))
      (node (ref "IC13") (pin "10") (pinfunction "PGND_10") (pintype "passive"))
      (node (ref "IC13") (pin "11") (pinfunction "PGND_11") (pintype "passive"))
      (node (ref "IC13") (pin "15") (pinfunction "AGND_15") (pintype "passive"))
      (node (ref "IC13") (pin "16") (pinfunction "NC_16") (pintype "passive"))
      (node (ref "IC13") (pin "5") (pinfunction "NC_5") (pintype "passive"))
      (node (ref "IC13") (pin "PAD") (pinfunction "PAD_GND_PAD") (pintype "passive"))
      (node (ref "IC14") (pin "5") (pinfunction "SGND_5") (pintype "passive"))
      (node (ref "IC14") (pin "9") (pinfunction "PGND_9") (pintype "passive"))
      (node (ref "IC14") (pin "PAD") (pinfunction "GND_PAD_PAD") (pintype "passive"))
      (node (ref "IC15") (pin "5") (pinfunction "SGND_5") (pintype "passive"))
      (node (ref "IC15") (pin "9") (pinfunction "PGND_9") (pintype "passive"))
      (node (ref "IC15") (pin "PAD") (pinfunction "GND_PAD_PAD") (pintype "passive"))
      (node (ref "IC21") (pin "1") (pinfunction "REF_1") (pintype "power_in"))
      (node (ref "IC21") (pin "2") (pinfunction "GND_2") (pintype "power_in"))
      (node (ref "IC22") (pin "1") (pinfunction "REF_1") (pintype "power_in"))
      (node (ref "IC22") (pin "2") (pinfunction "GND_2") (pintype "power_in"))
      (node (ref "IC24") (pin "1") (pinfunction "REF_1") (pintype "power_in"))
      (node (ref "IC24") (pin "2") (pinfunction "GND_2") (pintype "power_in"))
      (node (ref "Q2") (pin "1") (pinfunction "S_1") (pintype "passive"))
      (node (ref "Q2") (pin "2") (pinfunction "S_2") (pintype "passive"))
      (node (ref "Q2") (pin "3") (pinfunction "S_3") (pintype "passive"))
      (node (ref "Q4") (pin "1") (pinfunction "S_1") (pintype "passive"))
      (node (ref "Q4") (pin "2") (pinfunction "S_2") (pintype "passive"))
      (node (ref "Q4") (pin "3") (pinfunction "S_3") (pintype "passive"))
      (node (ref "R23") (pin "2") (pinfunction "2_2") (pintype "passive"))
      (node (ref "R24") (pin "1") (pinfunction "1_1") (pintype "passive"))
      (node (ref "R26") (pin "1") (pinfunction "1_1") (pintype "passive"))
      (node (ref "R31") (pin "1") (pinfunction "1_1") (pintype "passive"))
      (node (ref "R35") (pin "1") (pinfunction "1_1") (pintype "passive"))
      (node (ref "R36") (pin "1") (pinfunction "1_1") (pintype "passive"))
      (node (ref "R44") (pin "1") (pinfunction "1_1") (pintype "passive"))
    )
    (net (code "12") (name "Net-(C14-Pad2)") (class "Default")
      (node (ref "C14") (pin "2") (pinfunction "2_2") (pintype "passive"))
      (node (ref "R25") (pin "1") (pinfunction "1_1") (pintype "passive"))
    )
    (net (code "13") (name "Net-(C19-Pad2)") (class "Default")
      (node (ref "C19") (pin "2") (pinfunction "2_2") (pintype "passive"))
      (node (ref "R28") (pin "1") (pinfunction "1_1") (pintype "passive"))
    )
    (net (code "14") (name "Net-(C20-Pad2)") (class "Default")
      (node (ref "C20") (pin "2") (pinfunction "2_2") (pintype "passive"))
      (node (ref "R30") (pin "1") (pinfunction "1_1") (pintype "passive"))
    )
    (net (code "15") (name "Net-(C29-Pad2)") (class "Default")
      (node (ref "C29") (pin "2") (pinfunction "2_2") (pintype "passive"))
      (node (ref "R42") (pin "1") (pinfunction "1_1") (pintype "passive"))
    )
    (net (code "16") (name "Net-(C61-Pad2)") (class "Default")
      (node (ref "C61") (pin "2") (pinfunction "2_2") (pintype "passive"))
      (node (ref "R38") (pin "1") (pinfunction "1_1") (pintype "passive"))
    )
    (net (code "17") (name "Net-(D14-K)") (class "Default")
      (node (ref "C12") (pin "2") (pinfunction "2_2") (pintype "passive"))
      (node (ref "D14") (pin "2") (pinfunction "K_2") (pintype "passive"))
      (node (ref "IC14") (pin "12") (pinfunction "SW_12") (pintype "passive"))
      (node (ref "L1") (pin "1") (pinfunction "1_1") (pintype "passive"))
      (node (ref "Q1") (pin "1") (pinfunction "S_1") (pintype "passive"))
      (node (ref "Q1") (pin "2") (pinfunction "S_2") (pintype "passive"))
      (node (ref "Q1") (pin "3") (pinfunction "S_3") (pintype "passive"))
      (node (ref "Q2") (pin "5") (pinfunction "D_5") (pintype "passive"))
      (node (ref "Q2") (pin "6") (pinfunction "D_6") (pintype "passive"))
      (node (ref "Q2") (pin "7") (pinfunction "D_7") (pintype "passive"))
      (node (ref "Q2") (pin "8") (pinfunction "D_8") (pintype "passive"))
    )
    (net (code "18") (name "Net-(D15-A)") (class "Default")
      (node (ref "D15") (pin "1") (pinfunction "A_1") (pintype "passive"))
      (node (ref "R29") (pin "1") (pinfunction "1_1") (pintype "passive"))
    )
    (net (code "19") (name "Net-(D16-A)") (class "Default")
      (node (ref "D16") (pin "1") (pinfunction "A_1") (pintype "passive"))
      (node (ref "R34") (pin "1") (pinfunction "1_1") (pintype "passive"))
    )
    (net (code "20") (name "Net-(D18-K)") (class "Default")
      (node (ref "C25") (pin "2") (pinfunction "2_2") (pintype "passive"))
      (node (ref "D18") (pin "2") (pinfunction "K_2") (pintype "passive"))
      (node (ref "IC15") (pin "12") (pinfunction "SW_12") (pintype "passive"))
      (node (ref "L2") (pin "1") (pinfunction "1_1") (pintype "passive"))
      (node (ref "Q3") (pin "1") (pinfunction "S_1") (pintype "passive"))
      (node (ref "Q3") (pin "2") (pinfunction "S_2") (pintype "passive"))
      (node (ref "Q3") (pin "3") (pinfunction "S_3") (pintype "passive"))
      (node (ref "Q4") (pin "5") (pinfunction "D_5") (pintype "passive"))
      (node (ref "Q4") (pin "6") (pinfunction "D_6") (pintype "passive"))
      (node (ref "Q4") (pin "7") (pinfunction "D_7") (pintype "passive"))
      (node (ref "Q4") (pin "8") (pinfunction "D_8") (pintype "passive"))
    )
    (net (code "21") (name "Net-(D19-A)") (class "Default")
      (node (ref "D19") (pin "1") (pinfunction "A_1") (pintype "passive"))
      (node (ref "R41") (pin "1") (pinfunction "1_1") (pintype "passive"))
    )
    (net (code "22") (name "Net-(IC13-AVIN)") (class "Default")
      (node (ref "C13") (pin "2") (pinfunction "2_2") (pintype "passive"))
      (node (ref "IC13") (pin "14") (pinfunction "AVIN_14") (pintype "passive"))
      (node (ref "R16") (pin "1") (pinfunction "1_1") (pintype "passive"))
    )
    (net (code "23") (name "Net-(IC13-COMP)") (class "Default")
      (node (ref "IC13") (pin "4") (pinfunction "COMP_4") (pintype "passive"))
      (node (ref "R25") (pin "2") (pinfunction "2_2") (pintype "passive"))
    )
    (net (code "24") (name "Net-(IC13-FB)") (class "Default")
      (node (ref "IC13") (pin "2") (pinfunction "FB_2") (pintype "passive"))
      (node (ref "R17") (pin "1") (pinfunction "1_1") (pintype "passive"))
      (node (ref "R23") (pin "1") (pinfunction "1_1") (pintype "passive"))
    )
    (net (code "25") (name "Net-(IC13-SS{slash}TRK)") (class "Default")
      (node (ref "C16") (pin "2") (pinfunction "2_2") (pintype "passive"))
      (node (ref "IC13") (pin "1") (pinfunction "SS/TRK_1") (pintype "passive"))
    )
    (net (code "26") (name "Net-(IC13-SW-Pad8)") (class "Default")
      (node (ref "IC13") (pin "8") (pinfunction "SW_8") (pintype "passive"))
      (node (ref "IC13") (pin "9") (pinfunction "SW_9") (pintype "passive"))
      (node (ref "L8") (pin "1") (pinfunction "1_1") (pintype "passive"))
    )
    (net (code "27") (name "Net-(IC13-VCC)") (class "Default")
      (node (ref "C17") (pin "2") (pinfunction "2_2") (pintype "passive"))
      (node (ref "IC13") (pin "13") (pinfunction "VCC_13") (pintype "passive"))
    )
    (net (code "28") (name "Net-(IC14-BOOST)") (class "Default")
      (node (ref "C12") (pin "1") (pinfunction "1_1") (pintype "passive"))
      (node (ref "IC14") (pin "14") (pinfunction "BOOST_14") (pintype "passive"))
    )
    (net (code "29") (name "Net-(IC14-BP5)") (class "Default")
      (node (ref "C11") (pin "2") (pinfunction "2_2") (pintype "passive"))
      (node (ref "IC14") (pin "3") (pinfunction "BP5_3") (pintype "passive"))
    )
    (net (code "30") (name "Net-(IC14-BP10)") (class "Default")
      (node (ref "C256") (pin "1") (pinfunction "1_1") (pintype "passive"))
      (node (ref "IC14") (pin "11") (pinfunction "BP10_11") (pintype "passive"))
    )
    (net (code "31") (name "Net-(IC14-COMP)") (class "Default")
      (node (ref "C28") (pin "2") (pinfunction "2_2") (pintype "passive"))
      (node (ref "IC14") (pin "8") (pinfunction "COMP_8") (pintype "passive"))
      (node (ref "R30") (pin "2") (pinfunction "2_2") (pintype "passive"))
    )
    (net (code "32") (name "Net-(IC14-HDRV)") (class "Default")
      (node (ref "IC14") (pin "13") (pinfunction "HDRV_13") (pintype "passive"))
      (node (ref "Q1") (pin "4") (pinfunction "G_4") (pintype "passive"))
    )
    (net (code "33") (name "Net-(IC14-ILIM)") (class "Default")
      (node (ref "C10") (pin "1") (pinfunction "1_1") (pintype "passive"))
      (node (ref "IC14") (pin "16") (pinfunction "ILIM_16") (pintype "passive"))
      (node (ref "R15") (pin "1") (pinfunction "1_1") (pintype "passive"))
    )
    (net (code "34") (name "Net-(IC14-KFF)") (class "Default")
      (node (ref "IC14") (pin "1") (pinfunction "KFF_1") (pintype "passive"))
      (node (ref "R13") (pin "1") (pinfunction "1_1") (pintype "passive"))
    )
    (net (code "35") (name "Net-(IC14-LDRV)") (class "Default")
      (node (ref "IC14") (pin "10") (pinfunction "LDRV_10") (pintype "passive"))
      (node (ref "Q2") (pin "4") (pinfunction "G_4") (pintype "passive"))
    )
    (net (code "36") (name "Net-(IC14-RT)") (class "Default")
      (node (ref "IC14") (pin "2") (pinfunction "RT_2") (pintype "passive"))
      (node (ref "R24") (pin "2") (pinfunction "2_2") (pintype "passive"))
    )
    (net (code "37") (name "Net-(IC14-SS{slash}SD)") (class "Default")
      (node (ref "C15") (pin "2") (pinfunction "2_2") (pintype "passive"))
      (node (ref "IC14") (pin "6") (pinfunction "SS/SD_6") (pintype "passive"))
    )
    (net (code "38") (name "Net-(IC14-SYNC)") (class "Default")
      (node (ref "IC14") (pin "4") (pinfunction "SYNC_4") (pintype "passive"))
      (node (ref "R26") (pin "2") (pinfunction "2_2") (pintype "passive"))
    )
    (net (code "39") (name "Net-(IC14-VFB)") (class "Default")
      (node (ref "C19") (pin "1") (pinfunction "1_1") (pintype "passive"))
      (node (ref "C20") (pin "1") (pinfunction "1_1") (pintype "passive"))
      (node (ref "C28") (pin "1") (pinfunction "1_1") (pintype "passive"))
      (node (ref "IC14") (pin "7") (pinfunction "VFB_7") (pintype "passive"))
      (node (ref "R27") (pin "1") (pinfunction "1_1") (pintype "passive"))
      (node (ref "R31") (pin "2") (pinfunction "2_2") (pintype "passive"))
    )
    (net (code "40") (name "Net-(IC15-BOOST)") (class "Default")
      (node (ref "C25") (pin "1") (pinfunction "1_1") (pintype "passive"))
      (node (ref "IC15") (pin "14") (pinfunction "BOOST_14") (pintype "passive"))
    )
    (net (code "41") (name "Net-(IC15-BP5)") (class "Default")
      (node (ref "C24") (pin "2") (pinfunction "2_2") (pintype "passive"))
      (node (ref "IC15") (pin "3") (pinfunction "BP5_3") (pintype "passive"))
    )
    (net (code "42") (name "Net-(IC15-BP10)") (class "Default")
      (node (ref "C27") (pin "1") (pinfunction "1_1") (pintype "passive"))
      (node (ref "IC15") (pin "11") (pinfunction "BP10_11") (pintype "passive"))
    )
    (net (code "43") (name "Net-(IC15-COMP)") (class "Default")
      (node (ref "C193") (pin "2") (pinfunction "2_2") (pintype "passive"))
      (node (ref "IC15") (pin "8") (pinfunction "COMP_8") (pintype "passive"))
      (node (ref "R42") (pin "2") (pinfunction "2_2") (pintype "passive"))
    )
    (net (code "44") (name "Net-(IC15-HDRV)") (class "Default")
      (node (ref "IC15") (pin "13") (pinfunction "HDRV_13") (pintype "passive"))
      (node (ref "Q3") (pin "4") (pinfunction "G_4") (pintype "passive"))
    )
    (net (code "45") (name "Net-(IC15-ILIM)") (class "Default")
      (node (ref "C22") (pin "1") (pinfunction "1_1") (pintype "passive"))
      (node (ref "IC15") (pin "16") (pinfunction "ILIM_16") (pintype "passive"))
      (node (ref "R32") (pin "1") (pinfunction "1_1") (pintype "passive"))
    )
    (net (code "46") (name "Net-(IC15-KFF)") (class "Default")
      (node (ref "IC15") (pin "1") (pinfunction "KFF_1") (pintype "passive"))
      (node (ref "R33") (pin "1") (pinfunction "1_1") (pintype "passive"))
    )
    (net (code "47") (name "Net-(IC15-LDRV)") (class "Default")
      (node (ref "IC15") (pin "10") (pinfunction "LDRV_10") (pintype "passive"))
      (node (ref "Q4") (pin "4") (pinfunction "G_4") (pintype "passive"))
    )
    (net (code "48") (name "Net-(IC15-RT)") (class "Default")
      (node (ref "IC15") (pin "2") (pinfunction "RT_2") (pintype "passive"))
      (node (ref "R35") (pin "2") (pinfunction "2_2") (pintype "passive"))
    )
    (net (code "49") (name "Net-(IC15-SS{slash}SD)") (class "Default")
      (node (ref "C26") (pin "2") (pinfunction "2_2") (pintype "passive"))
      (node (ref "IC15") (pin "6") (pinfunction "SS/SD_6") (pintype "passive"))
    )
    (net (code "50") (name "Net-(IC15-SYNC)") (class "Default")
      (node (ref "IC15") (pin "4") (pinfunction "SYNC_4") (pintype "passive"))
      (node (ref "R36") (pin "2") (pinfunction "2_2") (pintype "passive"))
    )
    (net (code "51") (name "Net-(IC15-VFB)") (class "Default")
      (node (ref "C193") (pin "1") (pinfunction "1_1") (pintype "passive"))
      (node (ref "C29") (pin "1") (pinfunction "1_1") (pintype "passive"))
      (node (ref "C61") (pin "1") (pinfunction "1_1") (pintype "passive"))
      (node (ref "IC15") (pin "7") (pinfunction "VFB_7") (pintype "passive"))
      (node (ref "R37") (pin "1") (pinfunction "1_1") (pintype "passive"))
      (node (ref "R44") (pin "2") (pinfunction "2_2") (pintype "passive"))
    )
    (net (code "52") (name "Net-(IC21-IN+)") (class "Default")
      (node (ref "C140") (pin "2") (pinfunction "2_2") (pintype "passive"))
      (node (ref "IC21") (pin "4") (pinfunction "IN+_4") (pintype "passive"))
      (node (ref "R103") (pin "1") (pinfunction "1_1") (pintype "passive"))
    )
    (net (code "53") (name "Net-(IC21-IN-)") (class "Default")
      (node (ref "C140") (pin "1") (pinfunction "1_1") (pintype "passive"))
      (node (ref "IC21") (pin "5") (pinfunction "IN-_5") (pintype "passive"))
      (node (ref "R104") (pin "1") (pinfunction "1_1") (pintype "passive"))
    )
    (net (code "54") (name "Net-(IC22-IN+)") (class "Default")
      (node (ref "C241") (pin "2") (pinfunction "2_2") (pintype "passive"))
      (node (ref "IC22") (pin "4") (pinfunction "IN+_4") (pintype "passive"))
      (node (ref "R105") (pin "1") (pinfunction "1_1") (pintype "passive"))
    )
    (net (code "55") (name "Net-(IC22-IN-)") (class "Default")
      (node (ref "C241") (pin "1") (pinfunction "1_1") (pintype "passive"))
      (node (ref "IC22") (pin "5") (pinfunction "IN-_5") (pintype "passive"))
      (node (ref "R106") (pin "1") (pinfunction "1_1") (pintype "passive"))
    )
    (net (code "56") (name "Net-(IC24-IN+)") (class "Default")
      (node (ref "C242") (pin "2") (pinfunction "2_2") (pintype "passive"))
      (node (ref "IC24") (pin "4") (pinfunction "IN+_4") (pintype "passive"))
      (node (ref "R107") (pin "1") (pinfunction "1_1") (pintype "passive"))
    )
    (net (code "57") (name "Net-(IC24-IN-)") (class "Default")
      (node (ref "C242") (pin "1") (pinfunction "1_1") (pintype "passive"))
      (node (ref "IC24") (pin "5") (pinfunction "IN-_5") (pintype "passive"))
      (node (ref "R108") (pin "1") (pinfunction "1_1") (pintype "passive"))
    )
    (net (code "58") (name "Net-(L1-Pad2)") (class "Default")
      (node (ref "L1") (pin "2") (pinfunction "2_2") (pintype "passive"))
      (node (ref "R105") (pin "2") (pinfunction "2_2") (pintype "passive"))
      (node (ref "R97") (pin "2") (pinfunction "2_2") (pintype "passive"))
    )
    (net (code "59") (name "Net-(L2-Pad2)") (class "Default")
      (node (ref "L2") (pin "2") (pinfunction "2_2") (pintype "passive"))
      (node (ref "R107") (pin "2") (pinfunction "2_2") (pintype "passive"))
      (node (ref "R98") (pin "2") (pinfunction "2_2") (pintype "passive"))
    )
    (net (code "60") (name "Net-(L8-Pad2)") (class "Default")
      (node (ref "L8") (pin "2") (pinfunction "2_2") (pintype "passive"))
      (node (ref "R103") (pin "2") (pinfunction "2_2") (pintype "passive"))
      (node (ref "R96") (pin "2") (pinfunction "2_2") (pintype "passive"))
    )
    (net (code "61") (name "unconnected-(IC13-PGOOD-Pad3)") (class "Default")
      (node (ref "IC13") (pin "3") (pinfunction "PGOOD_3") (pintype "passive"))
    )
  )
)
